# LightBox_Schematic.net
KiCad netlist of a schematic drawn in EAGLE
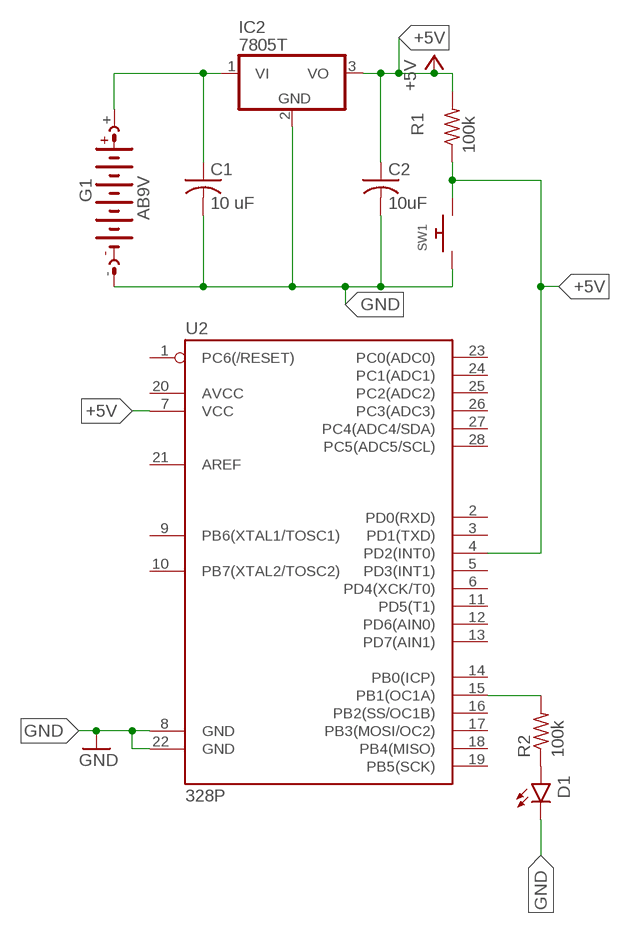
[diagram p0: schematic, sheet 1]

(export (version "E")
  (design (tool "Eeschema 10.0.6"))
  (components
    (comp (ref "C1")
      (value "10 uF")
      (footprint "eagle-import:C0805")
      (libsource (lib "eagle-import") (part "C-USC0805"))
    )
    (comp (ref "C2")
      (value "10uF")
      (footprint "eagle-import:C0805")
      (libsource (lib "eagle-import") (part "C-USC0805"))
    )
    (comp (ref "D1")
      (value "LED3MM")
      (footprint "eagle-import:LED_3MM")
      (libsource (lib "eagle-import") (part "LED3MM"))
    )
    (comp (ref "G1")
      (value "AB9V")
      (footprint "eagle-import:AB9V")
      (libsource (lib "eagle-import") (part "AB9V"))
    )
    (comp (ref "IC2")
      (value "7805T")
      (footprint "eagle-import:TO220H")
      (libsource (lib "eagle-import") (part "78T05"))
    )
    (comp (ref "R1")
      (value "100k")
      (footprint "eagle-import:R0805")
      (libsource (lib "eagle-import") (part "R-US_R0805"))
    )
    (comp (ref "R2")
      (value "100k")
      (footprint "eagle-import:R0805")
      (libsource (lib "eagle-import") (part "R-US_R0805"))
    )
    (comp (ref "SW1")
      (value "SWITCH_PUSHBUTTONEVQ-PE")
      (footprint "eagle-import:TACT_PANA-EVQ")
      (libsource (lib "eagle-import") (part "SWITCH_PUSHBUTTONEVQ-PE"))
    )
    (comp (ref "U2")
      (value "328P")
      (footprint "eagle-import:DIP28")
      (libsource (lib "eagle-import") (part "ATMEGA328P_PDIP"))
    )
  )
  (nets
    (net (code "1") (name "+5V") (class "Default")
      (node (ref "C2") (pin "1") (pinfunction "1_1") (pintype "passive"))
      (node (ref "IC2") (pin "3") (pinfunction "VO_3") (pintype "passive"))
      (node (ref "R1") (pin "1") (pinfunction "1_1") (pintype "passive"))
      (node (ref "R1") (pin "2") (pinfunction "2_2") (pintype "passive"))
      (node (ref "SW1") (pin "P$2") (pinfunction "P$2_P$2") (pintype "passive"))
      (node (ref "U2") (pin "4") (pinfunction "PD2(INT0)_4") (pintype "bidirectional"))
      (node (ref "U2") (pin "7") (pinfunction "VCC_7") (pintype "bidirectional"))
    )
    (net (code "2") (name "GND") (class "Default")
      (node (ref "C1") (pin "2") (pinfunction "2_2") (pintype "passive"))
      (node (ref "C2") (pin "2") (pinfunction "2_2") (pintype "passive"))
      (node (ref "D1") (pin "K") (pinfunction "C_K") (pintype "passive"))
      (node (ref "G1") (pin "-") (pinfunction "-_-") (pintype "passive"))
      (node (ref "IC2") (pin "2") (pinfunction "GND_2") (pintype "passive"))
      (node (ref "SW1") (pin "P$1") (pinfunction "P$1_P$1") (pintype "passive"))
      (node (ref "U2") (pin "22") (pinfunction "GND_22") (pintype "bidirectional"))
      (node (ref "U2") (pin "8") (pinfunction "GND_8") (pintype "bidirectional"))
    )
    (net (code "3") (name "Net-(D1-PadA)") (class "Default")
      (node (ref "D1") (pin "A") (pinfunction "A_A") (pintype "passive"))
      (node (ref "R2") (pin "1") (pinfunction "1_1") (pintype "passive"))
    )
    (net (code "4") (name "Net-(IC2-VI)") (class "Default")
      (node (ref "C1") (pin "1") (pinfunction "1_1") (pintype "passive"))
      (node (ref "G1") (pin "+") (pinfunction "+_+") (pintype "passive"))
      (node (ref "IC2") (pin "1") (pinfunction "VI_1") (pintype "input"))
    )
    (net (code "5") (name "Net-(U2-PB1(OC1A))") (class "Default")
      (node (ref "R2") (pin "2") (pinfunction "2_2") (pintype "passive"))
      (node (ref "U2") (pin "15") (pinfunction "PB1(OC1A)_15") (pintype "bidirectional"))
    )
    (net (code "6") (name "unconnected-(U2-AREF-Pad21)") (class "Default")
      (node (ref "U2") (pin "21") (pinfunction "AREF_21") (pintype "bidirectional"))
    )
    (net (code "7") (name "unconnected-(U2-AVCC-Pad20)") (class "Default")
      (node (ref "U2") (pin "20") (pinfunction "AVCC_20") (pintype "bidirectional"))
    )
    (net (code "8") (name "unconnected-(U2-PB0(ICP)-Pad14)") (class "Default")
      (node (ref "U2") (pin "14") (pinfunction "PB0(ICP)_14") (pintype "bidirectional"))
    )
    (net (code "9") (name "unconnected-(U2-PB2(SS{slash}OC1B)-Pad16)") (class "Default")
      (node (ref "U2") (pin "16") (pinfunction "PB2(SS/OC1B)_16") (pintype "bidirectional"))
    )
    (net (code "10") (name "unconnected-(U2-PB3(MOSI{slash}OC2)-Pad17)") (class "Default")
      (node (ref "U2") (pin "17") (pinfunction "PB3(MOSI/OC2)_17") (pintype "bidirectional"))
    )
    (net (code "11") (name "unconnected-(U2-PB4(MISO)-Pad18)") (class "Default")
      (node (ref "U2") (pin "18") (pinfunction "PB4(MISO)_18") (pintype "bidirectional"))
    )
    (net (code "12") (name "unconnected-(U2-PB5(SCK)-Pad19)") (class "Default")
      (node (ref "U2") (pin "19") (pinfunction "PB5(SCK)_19") (pintype "bidirectional"))
    )
    (net (code "13") (name "unconnected-(U2-PB6(XTAL1{slash}TOSC1)-Pad9)") (class "Default")
      (node (ref "U2") (pin "9") (pinfunction "PB6(XTAL1/TOSC1)_9") (pintype "bidirectional"))
    )
    (net (code "14") (name "unconnected-(U2-PB7(XTAL2{slash}TOSC2)-Pad10)") (class "Default")
      (node (ref "U2") (pin "10") (pinfunction "PB7(XTAL2/TOSC2)_10") (pintype "bidirectional"))
    )
    (net (code "15") (name "unconnected-(U2-PC0(ADC0)-Pad23)") (class "Default")
      (node (ref "U2") (pin "23") (pinfunction "PC0(ADC0)_23") (pintype "bidirectional"))
    )
    (net (code "16") (name "unconnected-(U2-PC1(ADC1)-Pad24)") (class "Default")
      (node (ref "U2") (pin "24") (pinfunction "PC1(ADC1)_24") (pintype "bidirectional"))
    )
    (net (code "17") (name "unconnected-(U2-PC2(ADC2)-Pad25)") (class "Default")
      (node (ref "U2") (pin "25") (pinfunction "PC2(ADC2)_25") (pintype "bidirectional"))
    )
    (net (code "18") (name "unconnected-(U2-PC3(ADC3)-Pad26)") (class "Default")
      (node (ref "U2") (pin "26") (pinfunction "PC3(ADC3)_26") (pintype "bidirectional"))
    )
    (net (code "19") (name "unconnected-(U2-PC4(ADC4{slash}SDA)-Pad27)") (class "Default")
      (node (ref "U2") (pin "27") (pinfunction "PC4(ADC4/SDA)_27") (pintype "bidirectional"))
    )
    (net (code "20") (name "unconnected-(U2-PC5(ADC5{slash}SCL)-Pad28)") (class "Default")
      (node (ref "U2") (pin "28") (pinfunction "PC5(ADC5/SCL)_28") (pintype "bidirectional"))
    )
    (net (code "21") (name "unconnected-(U2-PC6({slash}RESET)-Pad1)") (class "Default")
      (node (ref "U2") (pin "1") (pinfunction "PC6(/RESET)_1") (pintype "bidirectional"))
    )
    (net (code "22") (name "unconnected-(U2-PD0(RXD)-Pad2)") (class "Default")
      (node (ref "U2") (pin "2") (pinfunction "PD0(RXD)_2") (pintype "bidirectional"))
    )
    (net (code "23") (name "unconnected-(U2-PD1(TXD)-Pad3)") (class "Default")
      (node (ref "U2") (pin "3") (pinfunction "PD1(TXD)_3") (pintype "bidirectional"))
    )
    (net (code "24") (name "unconnected-(U2-PD3(INT1)-Pad5)") (class "Default")
      (node (ref "U2") (pin "5") (pinfunction "PD3(INT1)_5") (pintype "bidirectional"))
    )
    (net (code "25") (name "unconnected-(U2-PD4(XCK{slash}T0)-Pad6)") (class "Default")
      (node (ref "U2") (pin "6") (pinfunction "PD4(XCK/T0)_6") (pintype "bidirectional"))
    )
    (net (code "26") (name "unconnected-(U2-PD5(T1)-Pad11)") (class "Default")
      (node (ref "U2") (pin "11") (pinfunction "PD5(T1)_11") (pintype "bidirectional"))
    )
    (net (code "27") (name "unconnected-(U2-PD6(AIN0)-Pad12)") (class "Default")
      (node (ref "U2") (pin "12") (pinfunction "PD6(AIN0)_12") (pintype "bidirectional"))
    )
    (net (code "28") (name "unconnected-(U2-PD7(AIN1)-Pad13)") (class "Default")
      (node (ref "U2") (pin "13") (pinfunction "PD7(AIN1)_13") (pintype "bidirectional"))
    )
  )
)
